# Sheet2.net
KiCad netlist of a schematic drawn in Altium Designer
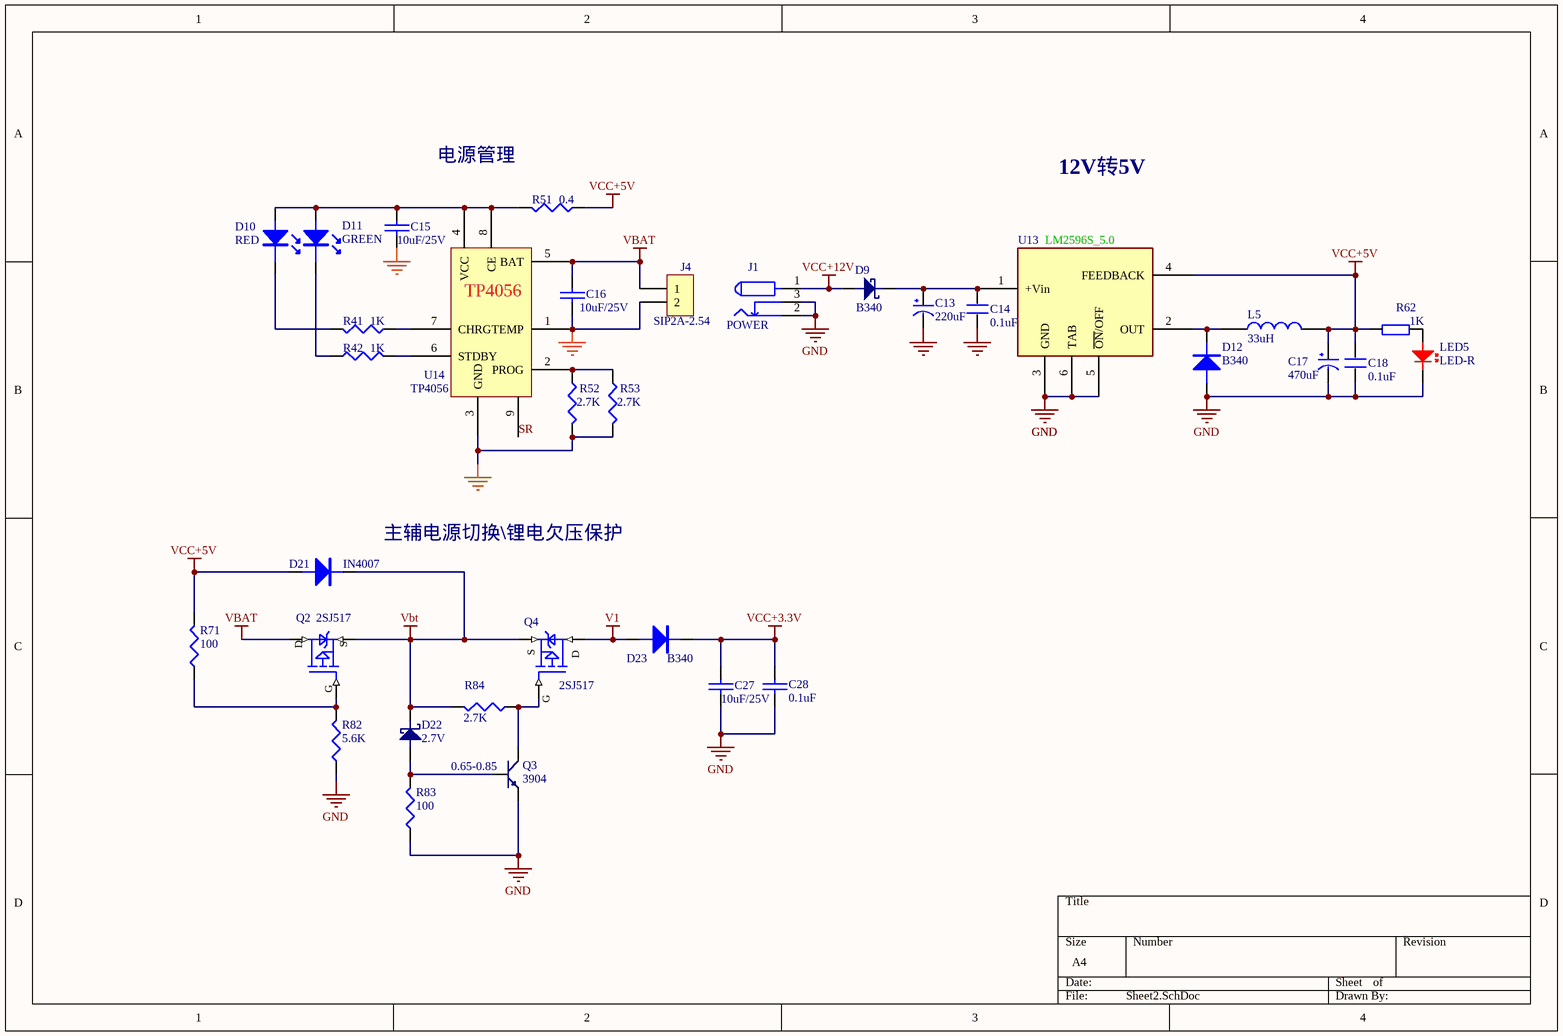
[diagram p0: Sheet2.SchDoc]

(export (version "E")
  (design (tool "Eeschema 10.0.6"))
  (components
    (comp (ref "C13") (value "220uF") (footprint "RB3.5") (libsource (lib "战舰STM32开发板底板") (part "CAP")))
    (comp (ref "C14") (value "0.1uF") (footprint "0805") (libsource (lib "mylib") (part "C")))
    (comp (ref "C15") (value "10uF/25V") (footprint "0805") (libsource (lib "*") (part "CAP")))
    (comp (ref "C16") (value "10uF/25V") (footprint "0805") (libsource (lib "*") (part "CAP")))
    (comp (ref "C17") (value "470uF") (footprint "RB3.5") (libsource (lib "战舰STM32开发板底板") (part "CAP")))
    (comp (ref "C18") (value "0.1uF") (footprint "0805") (libsource (lib "mylib") (part "C")))
    (comp (ref "C27") (value "10uF/25V") (footprint "0805") (libsource (lib "*") (part "CAP")))
    (comp (ref "C28") (value "0.1uF") (footprint "0805") (libsource (lib "INSPUR_SCH") (part "CAP")))
    (comp (ref "D9")
      (value "B340")
      (footprint "SMB")
      (description "肖特基二极管")
      (libsource (lib "mylib") (part "1N5824(SS54)"))
    )
    (comp (ref "D10") (value "RED") (footprint "LED-0805") (libsource (lib "*") (part "LED")))
    (comp (ref "D11") (value "GREEN") (footprint "LED-0805") (libsource (lib "*") (part "LED")))
    (comp (ref "D12") (value "B340") (footprint "SMB") (libsource (lib "INSPUR_SCH") (part "DIODE")))
    (comp (ref "D21")
      (value "IN4007")
      (footprint "SMA(DO-214AC)")
      (libsource (lib "INSPUR_SCH") (part "DIODE"))
    )
    (comp (ref "D22")
      (value "2.7V")
      (footprint "sod-123")
      (description "3V稳压管")
      (libsource (lib "mylib") (part "1N5824(SS54)"))
    )
    (comp (ref "D23") (value "B340") (footprint "SMB") (libsource (lib "INSPUR_SCH") (part "DIODE")))
    (comp (ref "J1") (value "POWER") (footprint "DC10B") (libsource (lib "战舰STM32开发板底板") (part "POW")))
    (comp (ref "J4") (value "SIP2A-2.54") (footprint "2.54") (libsource (lib "*") (part "SIP2A-2.50（带槽）")))
    (comp (ref "L5") (value "33uH") (footprint "INDUCTOR-1212") (libsource (lib "mylib") (part "INDUCTOR")))
    (comp (ref "LED5")
      (value "LED-R")
      (footprint "LED-0805")
      (description "红色LED")
      (libsource (lib "mylib") (part "LED-RED"))
    )
    (comp (ref "Q2") (value "2SJ517") (footprint "SOT-89") (libsource (lib "*") (part "MOSFET P_1")))
    (comp (ref "Q3")
      (value "3904")
      (footprint "SOT-23")
      (description "8050/BCW846/BCW847")
      (libsource (lib "mylib") (part "NPN"))
    )
    (comp (ref "Q4") (value "2SJ517") (footprint "SOT-89") (libsource (lib "*") (part "MOSFET P_1")))
    (comp (ref "R41") (value "1K") (footprint "0805") (libsource (lib "*") (part "RES1")))
    (comp (ref "R42") (value "1K") (footprint "0805") (libsource (lib "*") (part "RES1")))
    (comp (ref "R51") (value "0.4") (footprint "1206") (libsource (lib "*") (part "RES1")))
    (comp (ref "R52") (value "2.7K") (footprint "0805") (libsource (lib "*") (part "RES1")))
    (comp (ref "R53") (value "2.7K") (footprint "0805") (libsource (lib "*") (part "RES1")))
    (comp (ref "R62") (value "1K") (footprint "0805") (libsource (lib "mylib") (part "Res")))
    (comp (ref "R71")
      (value "100")
      (footprint "0805")
      (description "Resistor")
      (libsource (lib "*") (part "RESISTOR"))
    )
    (comp (ref "R82")
      (value "5.6K")
      (footprint "0805")
      (description "Resistor")
      (libsource (lib "*") (part "RESISTOR"))
    )
    (comp (ref "R83")
      (value "100")
      (footprint "0805")
      (description "Resistor")
      (libsource (lib "*") (part "RESISTOR"))
    )
    (comp (ref "R84")
      (value "2.7K")
      (footprint "0805")
      (description "Resistor")
      (libsource (lib "*") (part "RESISTOR"))
    )
    (comp (ref "U13")
      (value "LM2596S_5.0")
      (footprint "TO-263-5")
      (description "3A开关电源芯片")
      (libsource (lib "Zhuangzaiji") (part "LM2596S_5.0"))
    )
    (comp (ref "U14") (value "TP4056") (footprint "SO8E") (libsource (lib "*") (part "TP4056")))
  )
  (nets
    (net (code "1") (name "/SR") (class "Default") (node (ref "U14") (pin "9") (pintype "passive")))
    (net (code "2") (name "GND") (class "Default")
      (node (ref "C13") (pin "2") (pinfunction "GND_2") (pintype "passive"))
      (node (ref "C14") (pin "1") (pintype "passive"))
      (node (ref "C15") (pin "2") (pinfunction "2_2") (pintype "passive"))
      (node (ref "C16") (pin "2") (pinfunction "2_2") (pintype "passive"))
      (node (ref "C17") (pin "2") (pinfunction "GND_2") (pintype "passive"))
      (node (ref "C18") (pin "1") (pintype "passive"))
      (node (ref "C27") (pin "2") (pinfunction "2_2") (pintype "passive"))
      (node (ref "C28") (pin "2") (pinfunction "2_2") (pintype "passive"))
      (node (ref "D12") (pin "1") (pinfunction "A_1") (pintype "passive"))
      (node (ref "J1") (pin "2") (pintype "passive"))
      (node (ref "J1") (pin "3") (pintype "passive"))
      (node (ref "J4") (pin "2") (pinfunction "2_2") (pintype "passive"))
      (node (ref "LED5") (pin "2") (pintype "passive"))
      (node (ref "Q3") (pin "1") (pinfunction "E_1") (pintype "passive"))
      (node (ref "R52") (pin "2") (pinfunction "2_2") (pintype "passive"))
      (node (ref "R53") (pin "2") (pinfunction "2_2") (pintype "passive"))
      (node (ref "R82") (pin "1") (pinfunction "1_1") (pintype "passive"))
      (node (ref "R83") (pin "1") (pinfunction "1_1") (pintype "passive"))
      (node (ref "U13") (pin "3") (pinfunction "GND_3") (pintype "passive"))
      (node (ref "U13") (pin "5") (pinfunction "~{ON}/OFF_5") (pintype "passive"))
      (node (ref "U13") (pin "6") (pinfunction "TAB_6") (pintype "passive"))
      (node (ref "U14") (pin "1") (pinfunction "TEMP_1") (pintype "passive"))
      (node (ref "U14") (pin "3") (pinfunction "GND_3") (pintype "passive"))
    )
    (net (code "3") (name "Net-(C13-VCC)") (class "Default")
      (node (ref "C13") (pin "1") (pinfunction "VCC_1") (pintype "passive"))
      (node (ref "C14") (pin "2") (pintype "passive"))
      (node (ref "D9") (pin "2") (pintype "passive"))
      (node (ref "U13") (pin "1") (pinfunction "+Vin_1") (pintype "passive"))
    )
    (net (code "4") (name "Net-(D10-Pad2)") (class "Default")
      (node (ref "D10") (pin "2") (pinfunction "2_2") (pintype "passive"))
      (node (ref "R41") (pin "2") (pinfunction "2_2") (pintype "passive"))
    )
    (net (code "5") (name "Net-(D11-Pad2)") (class "Default")
      (node (ref "D11") (pin "2") (pinfunction "2_2") (pintype "passive"))
      (node (ref "R42") (pin "1") (pinfunction "1_1") (pintype "passive"))
    )
    (net (code "6") (name "Net-(D12-K)") (class "Default")
      (node (ref "D12") (pin "2") (pinfunction "K_2") (pintype "passive"))
      (node (ref "L5") (pin "1") (pinfunction "1_1") (pintype "passive"))
      (node (ref "U13") (pin "2") (pinfunction "OUT_2") (pintype "passive"))
    )
    (net (code "7") (name "Net-(LED5-Pad1)") (class "Default")
      (node (ref "LED5") (pin "1") (pintype "passive"))
      (node (ref "R62") (pin "2") (pintype "passive"))
    )
    (net (code "8") (name "Net-(Q2-G)") (class "Default")
      (node (ref "Q2") (pin "1") (pinfunction "G_1") (pintype "input"))
      (node (ref "R71") (pin "1") (pinfunction "1_1") (pintype "passive"))
      (node (ref "R82") (pin "2") (pinfunction "2_2") (pintype "passive"))
    )
    (net (code "9") (name "Net-(Q3-B)") (class "Default")
      (node (ref "D22") (pin "1") (pintype "passive"))
      (node (ref "Q3") (pin "2") (pinfunction "B_2") (pintype "passive"))
      (node (ref "R83") (pin "2") (pinfunction "2_2") (pintype "passive"))
    )
    (net (code "10") (name "Net-(Q3-C)") (class "Default")
      (node (ref "Q3") (pin "3") (pinfunction "C_3") (pintype "passive"))
      (node (ref "Q4") (pin "1") (pinfunction "G_1") (pintype "input"))
      (node (ref "R84") (pin "1") (pinfunction "1_1") (pintype "passive"))
    )
    (net (code "11") (name "Net-(U14-CE)") (class "Default")
      (node (ref "C15") (pin "1") (pinfunction "1_1") (pintype "passive"))
      (node (ref "D10") (pin "1") (pinfunction "1_1") (pintype "passive"))
      (node (ref "D11") (pin "1") (pinfunction "1_1") (pintype "passive"))
      (node (ref "R51") (pin "2") (pinfunction "2_2") (pintype "passive"))
      (node (ref "U14") (pin "4") (pinfunction "VCC_4") (pintype "passive"))
      (node (ref "U14") (pin "8") (pinfunction "CE_8") (pintype "passive"))
    )
    (net (code "12") (name "Net-(U14-CHRG)") (class "Default")
      (node (ref "R41") (pin "1") (pinfunction "1_1") (pintype "passive"))
      (node (ref "U14") (pin "7") (pinfunction "CHRG_7") (pintype "passive"))
    )
    (net (code "13") (name "Net-(U14-PROG)") (class "Default")
      (node (ref "R52") (pin "1") (pinfunction "1_1") (pintype "passive"))
      (node (ref "R53") (pin "1") (pinfunction "1_1") (pintype "passive"))
      (node (ref "U14") (pin "2") (pinfunction "PROG_2") (pintype "passive"))
    )
    (net (code "14") (name "Net-(U14-STDBY)") (class "Default")
      (node (ref "R42") (pin "2") (pinfunction "2_2") (pintype "passive"))
      (node (ref "U14") (pin "6") (pinfunction "STDBY_6") (pintype "passive"))
    )
    (net (code "15") (name "V1") (class "Default")
      (node (ref "D23") (pin "1") (pinfunction "A_1") (pintype "passive"))
      (node (ref "Q4") (pin "2") (pinfunction "D_2") (pintype "input"))
    )
    (net (code "16") (name "VBAT") (class "Default")
      (node (ref "C16") (pin "1") (pinfunction "1_1") (pintype "passive"))
      (node (ref "J4") (pin "1") (pinfunction "1_1") (pintype "passive"))
      (node (ref "Q2") (pin "2") (pinfunction "D_2") (pintype "input"))
      (node (ref "U14") (pin "5") (pinfunction "BAT_5") (pintype "passive"))
    )
    (net (code "17") (name "VCC+3.3V") (class "Default")
      (node (ref "C27") (pin "1") (pinfunction "1_1") (pintype "passive"))
      (node (ref "C28") (pin "1") (pinfunction "1_1") (pintype "passive"))
      (node (ref "D23") (pin "2") (pinfunction "K_2") (pintype "passive"))
    )
    (net (code "18") (name "VCC+5V") (class "Default")
      (node (ref "C17") (pin "1") (pinfunction "VCC_1") (pintype "passive"))
      (node (ref "C18") (pin "2") (pintype "passive"))
      (node (ref "D21") (pin "1") (pinfunction "A_1") (pintype "passive"))
      (node (ref "L5") (pin "2") (pinfunction "2_2") (pintype "passive"))
      (node (ref "R51") (pin "1") (pinfunction "1_1") (pintype "passive"))
      (node (ref "R62") (pin "1") (pintype "passive"))
      (node (ref "R71") (pin "2") (pinfunction "2_2") (pintype "passive"))
      (node (ref "U13") (pin "4") (pinfunction "FEEDBACK_4") (pintype "passive"))
    )
    (net (code "19") (name "VCC+12V") (class "Default")
      (node (ref "D9") (pin "1") (pintype "passive"))
      (node (ref "J1") (pin "1") (pintype "passive"))
    )
    (net (code "20") (name "Vbt") (class "Default")
      (node (ref "D21") (pin "2") (pinfunction "K_2") (pintype "passive"))
      (node (ref "D22") (pin "2") (pintype "passive"))
      (node (ref "Q2") (pin "3") (pinfunction "S_3") (pintype "input"))
      (node (ref "Q4") (pin "3") (pinfunction "S_3") (pintype "input"))
      (node (ref "R84") (pin "2") (pinfunction "2_2") (pintype "passive"))
    )
  )
)
